# SCH-2-Main_Controls.net
KiCad netlist of a schematic drawn in Altium Designer
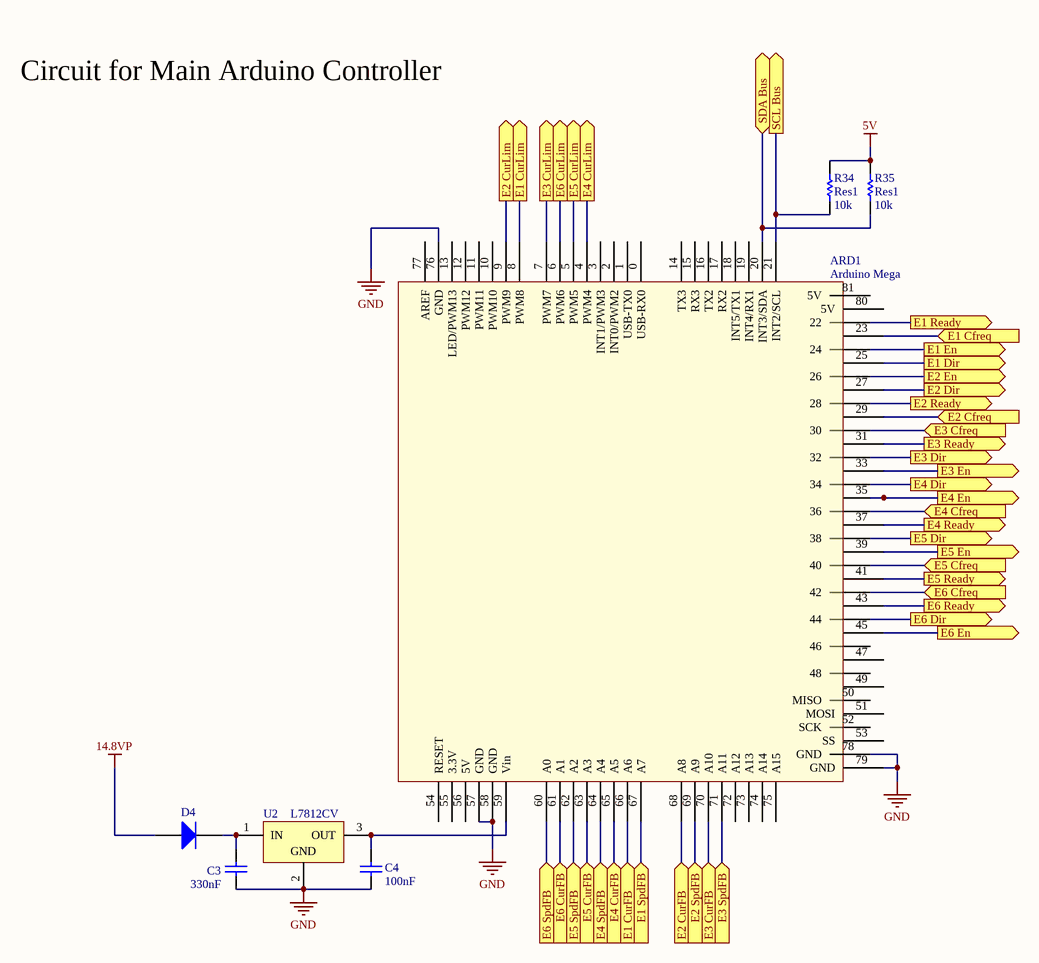
[diagram p0: SCH-2-Main Controls.SchDoc]

(export (version "E")
  (design (tool "Eeschema 10.0.6"))
  (components
    (comp (ref "ARD1")
      (value "Arduino Mega")
      (footprint "Arduino Mega")
      (libsource (lib "RSX_Schematics") (part "Arduino Mega"))
    )
    (comp (ref "C3")
      (value "330nF")
      (footprint "1608[0603]")
      (description "Capacitor")
      (fields (field (name "Comment") "Cap") (field (name "PUBLISHER") "Altium Limited"))
      (libsource (lib "Miscellaneous Devices") (part "Cap"))
    )
    (comp (ref "C4")
      (value "100nF")
      (footprint "1608[0603]")
      (description "Capacitor")
      (fields (field (name "Comment") "Cap") (field (name "PUBLISHER") "Altium Limited"))
      (libsource (lib "Miscellaneous Devices") (part "Cap"))
    )
    (comp (ref "D4")
      (value "Diode 1N4001")
      (footprint "DO-41")
      (description "1 Amp General Purpose Rectifier")
      (fields (field (name "PUBLISHER") "Altium Limited"))
      (libsource (lib "Miscellaneous Devices") (part "Diode 1N4001"))
    )
    (comp (ref "R34")
      (value "Res1")
      (footprint "RESC1608X06N_0603")
      (description "Resistor")
      (fields (field (name "ALTIUM_VALUE") "10k") (field (name "PUBLISHER") "Altium Limited"))
      (libsource (lib "RSX_Resistors") (part "Res1"))
    )
    (comp (ref "R35")
      (value "Res1")
      (footprint "RESC1608X06N_0603")
      (description "Resistor")
      (fields (field (name "ALTIUM_VALUE") "10k") (field (name "PUBLISHER") "Altium Limited"))
      (libsource (lib "RSX_Resistors") (part "Res1"))
    )
    (comp (ref "U2")
      (value "L7812CV")
      (footprint "TO220")
      (description "Positive Voltage Regulator, 12V, 3-Pin TO-220")
      (libsource (lib "Altium Content Vault") (part "PM-REG-L4940-SIL3"))
    )
  )
  (nets
    (net (code "1") (name "/E1 Cfreq") (class "Default")
      (node (ref "ARD1") (pin "23") (pinfunction "23_23") (pintype "passive"))
    )
    (net (code "2") (name "/E1 CurFB") (class "Default")
      (node (ref "ARD1") (pin "66") (pinfunction "A6_66") (pintype "passive"))
    )
    (net (code "3") (name "/E1 CurLim") (class "Default")
      (node (ref "ARD1") (pin "8") (pinfunction "PWM8_8") (pintype "passive"))
    )
    (net (code "4") (name "/E1 Dir") (class "Default")
      (node (ref "ARD1") (pin "25") (pinfunction "25_25") (pintype "passive"))
    )
    (net (code "5") (name "/E1 En") (class "Default")
      (node (ref "ARD1") (pin "24") (pinfunction "24_24") (pintype "passive"))
    )
    (net (code "6") (name "/E1 Ready") (class "Default")
      (node (ref "ARD1") (pin "22") (pinfunction "22_22") (pintype "passive"))
    )
    (net (code "7") (name "/E1 SpdFB") (class "Default")
      (node (ref "ARD1") (pin "67") (pinfunction "A7_67") (pintype "passive"))
    )
    (net (code "8") (name "/E2 Cfreq") (class "Default")
      (node (ref "ARD1") (pin "29") (pinfunction "29_29") (pintype "passive"))
    )
    (net (code "9") (name "/E2 CurFB") (class "Default")
      (node (ref "ARD1") (pin "68") (pinfunction "A8_68") (pintype "passive"))
    )
    (net (code "10") (name "/E2 CurLim") (class "Default")
      (node (ref "ARD1") (pin "9") (pinfunction "PWM9_9") (pintype "passive"))
    )
    (net (code "11") (name "/E2 Dir") (class "Default")
      (node (ref "ARD1") (pin "27") (pinfunction "27_27") (pintype "passive"))
    )
    (net (code "12") (name "/E2 En") (class "Default")
      (node (ref "ARD1") (pin "26") (pinfunction "26_26") (pintype "passive"))
    )
    (net (code "13") (name "/E2 Ready") (class "Default")
      (node (ref "ARD1") (pin "28") (pinfunction "28_28") (pintype "passive"))
    )
    (net (code "14") (name "/E2 SpdFB") (class "Default")
      (node (ref "ARD1") (pin "69") (pinfunction "A9_69") (pintype "passive"))
    )
    (net (code "15") (name "/E3 Cfreq") (class "Default")
      (node (ref "ARD1") (pin "30") (pinfunction "30_30") (pintype "passive"))
    )
    (net (code "16") (name "/E3 CurFB") (class "Default")
      (node (ref "ARD1") (pin "70") (pinfunction "A10_70") (pintype "passive"))
    )
    (net (code "17") (name "/E3 CurLim") (class "Default")
      (node (ref "ARD1") (pin "7") (pinfunction "PWM7_7") (pintype "passive"))
    )
    (net (code "18") (name "/E3 Dir") (class "Default")
      (node (ref "ARD1") (pin "32") (pinfunction "32_32") (pintype "passive"))
    )
    (net (code "19") (name "/E3 En") (class "Default")
      (node (ref "ARD1") (pin "33") (pinfunction "33_33") (pintype "passive"))
    )
    (net (code "20") (name "/E3 Ready") (class "Default")
      (node (ref "ARD1") (pin "31") (pinfunction "31_31") (pintype "passive"))
    )
    (net (code "21") (name "/E3 SpdFB") (class "Default")
      (node (ref "ARD1") (pin "71") (pinfunction "A11_71") (pintype "passive"))
    )
    (net (code "22") (name "/E4 Cfreq") (class "Default")
      (node (ref "ARD1") (pin "36") (pinfunction "36_36") (pintype "passive"))
    )
    (net (code "23") (name "/E4 CurFB") (class "Default")
      (node (ref "ARD1") (pin "65") (pinfunction "A5_65") (pintype "passive"))
    )
    (net (code "24") (name "/E4 CurLim") (class "Default")
      (node (ref "ARD1") (pin "4") (pinfunction "PWM4_4") (pintype "passive"))
    )
    (net (code "25") (name "/E4 Dir") (class "Default")
      (node (ref "ARD1") (pin "34") (pinfunction "34_34") (pintype "passive"))
    )
    (net (code "26") (name "/E4 En") (class "Default")
      (node (ref "ARD1") (pin "35") (pinfunction "35_35") (pintype "passive"))
    )
    (net (code "27") (name "/E4 Ready") (class "Default")
      (node (ref "ARD1") (pin "37") (pinfunction "37_37") (pintype "passive"))
    )
    (net (code "28") (name "/E4 SpdFB") (class "Default")
      (node (ref "ARD1") (pin "64") (pinfunction "A4_64") (pintype "passive"))
    )
    (net (code "29") (name "/E5 Cfreq") (class "Default")
      (node (ref "ARD1") (pin "40") (pinfunction "40_40") (pintype "passive"))
    )
    (net (code "30") (name "/E5 CurFB") (class "Default")
      (node (ref "ARD1") (pin "63") (pinfunction "A3_63") (pintype "passive"))
    )
    (net (code "31") (name "/E5 CurLim") (class "Default")
      (node (ref "ARD1") (pin "5") (pinfunction "PWM5_5") (pintype "passive"))
    )
    (net (code "32") (name "/E5 Dir") (class "Default")
      (node (ref "ARD1") (pin "38") (pinfunction "38_38") (pintype "passive"))
    )
    (net (code "33") (name "/E5 En") (class "Default")
      (node (ref "ARD1") (pin "39") (pinfunction "39_39") (pintype "passive"))
    )
    (net (code "34") (name "/E5 Ready") (class "Default")
      (node (ref "ARD1") (pin "41") (pinfunction "41_41") (pintype "passive"))
    )
    (net (code "35") (name "/E5 SpdFB") (class "Default")
      (node (ref "ARD1") (pin "62") (pinfunction "A2_62") (pintype "passive"))
    )
    (net (code "36") (name "/E6 Cfreq") (class "Default")
      (node (ref "ARD1") (pin "42") (pinfunction "42_42") (pintype "passive"))
    )
    (net (code "37") (name "/E6 CurFB") (class "Default")
      (node (ref "ARD1") (pin "61") (pinfunction "A1_61") (pintype "passive"))
    )
    (net (code "38") (name "/E6 CurLim") (class "Default")
      (node (ref "ARD1") (pin "6") (pinfunction "PWM6_6") (pintype "passive"))
    )
    (net (code "39") (name "/E6 Dir") (class "Default")
      (node (ref "ARD1") (pin "44") (pinfunction "44_44") (pintype "passive"))
    )
    (net (code "40") (name "/E6 En") (class "Default")
      (node (ref "ARD1") (pin "45") (pinfunction "45_45") (pintype "passive"))
    )
    (net (code "41") (name "/E6 Ready") (class "Default")
      (node (ref "ARD1") (pin "43") (pinfunction "43_43") (pintype "passive"))
    )
    (net (code "42") (name "/E6 SpdFB") (class "Default")
      (node (ref "ARD1") (pin "60") (pinfunction "A0_60") (pintype "passive"))
    )
    (net (code "43") (name "/SCL Bus") (class "Default")
      (node (ref "ARD1") (pin "21") (pinfunction "INT2/SCL_21") (pintype "passive"))
      (node (ref "R34") (pin "1") (pinfunction "1_1") (pintype "passive"))
    )
    (net (code "44") (name "/SDA Bus") (class "Default")
      (node (ref "ARD1") (pin "20") (pinfunction "INT3/SDA_20") (pintype "passive"))
      (node (ref "R35") (pin "1") (pinfunction "1_1") (pintype "passive"))
    )
    (net (code "45") (name "5V") (class "Default")
      (node (ref "R34") (pin "2") (pinfunction "2_2") (pintype "passive"))
      (node (ref "R35") (pin "2") (pinfunction "2_2") (pintype "passive"))
    )
    (net (code "46") (name "14.8VP") (class "Default")
      (node (ref "D4") (pin "1") (pinfunction "A_1") (pintype "passive"))
    )
    (net (code "47") (name "GND") (class "Default")
      (node (ref "ARD1") (pin "57") (pinfunction "GND_57") (pintype "passive"))
      (node (ref "ARD1") (pin "58") (pinfunction "GND_58") (pintype "passive"))
      (node (ref "ARD1") (pin "76") (pinfunction "GND_76") (pintype "passive"))
      (node (ref "ARD1") (pin "78") (pinfunction "GND_78") (pintype "passive"))
      (node (ref "ARD1") (pin "79") (pinfunction "GND_79") (pintype "passive"))
      (node (ref "C3") (pin "2") (pinfunction "2_2") (pintype "passive"))
      (node (ref "C4") (pin "2") (pinfunction "2_2") (pintype "passive"))
      (node (ref "U2") (pin "2") (pinfunction "GND_2") (pintype "power_in"))
    )
    (net (code "48") (name "Net-(ARD1-Vin)") (class "Default")
      (node (ref "ARD1") (pin "59") (pinfunction "Vin_59") (pintype "passive"))
      (node (ref "C4") (pin "1") (pinfunction "1_1") (pintype "passive"))
      (node (ref "U2") (pin "3") (pinfunction "OUT_3") (pintype "power_in"))
    )
    (net (code "49") (name "Net-(D4-K)") (class "Default")
      (node (ref "C3") (pin "1") (pinfunction "1_1") (pintype "passive"))
      (node (ref "D4") (pin "2") (pinfunction "K_2") (pintype "passive"))
      (node (ref "U2") (pin "1") (pinfunction "IN_1") (pintype "power_in"))
    )
    (net (code "50") (name "unconnected-(ARD1-3.3V-Pad55)") (class "Default")
      (node (ref "ARD1") (pin "55") (pinfunction "3.3V_55") (pintype "passive"))
    )
    (net (code "51") (name "unconnected-(ARD1-5V-Pad56)") (class "Default")
      (node (ref "ARD1") (pin "56") (pinfunction "5V_56") (pintype "passive"))
    )
    (net (code "52") (name "unconnected-(ARD1-5V-Pad80)") (class "Default")
      (node (ref "ARD1") (pin "80") (pinfunction "5V_80") (pintype "passive"))
    )
    (net (code "53") (name "unconnected-(ARD1-5V-Pad81)") (class "Default")
      (node (ref "ARD1") (pin "81") (pinfunction "5V_81") (pintype "passive"))
    )
    (net (code "54") (name "unconnected-(ARD1-A12-Pad72)") (class "Default")
      (node (ref "ARD1") (pin "72") (pinfunction "A12_72") (pintype "passive"))
    )
    (net (code "55") (name "unconnected-(ARD1-A13-Pad73)") (class "Default")
      (node (ref "ARD1") (pin "73") (pinfunction "A13_73") (pintype "passive"))
    )
    (net (code "56") (name "unconnected-(ARD1-A14-Pad74)") (class "Default")
      (node (ref "ARD1") (pin "74") (pinfunction "A14_74") (pintype "passive"))
    )
    (net (code "57") (name "unconnected-(ARD1-A15-Pad75)") (class "Default")
      (node (ref "ARD1") (pin "75") (pinfunction "A15_75") (pintype "passive"))
    )
    (net (code "58") (name "unconnected-(ARD1-AREF-Pad77)") (class "Default")
      (node (ref "ARD1") (pin "77") (pinfunction "AREF_77") (pintype "passive"))
    )
    (net (code "59") (name "unconnected-(ARD1-INT0{slash}PWM2-Pad2)") (class "Default")
      (node (ref "ARD1") (pin "2") (pinfunction "INT0/PWM2_2") (pintype "passive"))
    )
    (net (code "60") (name "unconnected-(ARD1-INT1{slash}PWM3-Pad3)") (class "Default")
      (node (ref "ARD1") (pin "3") (pinfunction "INT1/PWM3_3") (pintype "passive"))
    )
    (net (code "61") (name "unconnected-(ARD1-INT4{slash}RX1-Pad19)") (class "Default")
      (node (ref "ARD1") (pin "19") (pinfunction "INT4/RX1_19") (pintype "passive"))
    )
    (net (code "62") (name "unconnected-(ARD1-INT5{slash}TX1-Pad18)") (class "Default")
      (node (ref "ARD1") (pin "18") (pinfunction "INT5/TX1_18") (pintype "passive"))
    )
    (net (code "63") (name "unconnected-(ARD1-LED{slash}PWM13-Pad13)") (class "Default")
      (node (ref "ARD1") (pin "13") (pinfunction "LED/PWM13_13") (pintype "passive"))
    )
    (net (code "64") (name "unconnected-(ARD1-MISO-Pad50)") (class "Default")
      (node (ref "ARD1") (pin "50") (pinfunction "MISO_50") (pintype "passive"))
    )
    (net (code "65") (name "unconnected-(ARD1-MOSI-Pad51)") (class "Default")
      (node (ref "ARD1") (pin "51") (pinfunction "MOSI_51") (pintype "passive"))
    )
    (net (code "66") (name "unconnected-(ARD1-PWM10-Pad10)") (class "Default")
      (node (ref "ARD1") (pin "10") (pinfunction "PWM10_10") (pintype "passive"))
    )
    (net (code "67") (name "unconnected-(ARD1-PWM11-Pad11)") (class "Default")
      (node (ref "ARD1") (pin "11") (pinfunction "PWM11_11") (pintype "passive"))
    )
    (net (code "68") (name "unconnected-(ARD1-PWM12-Pad12)") (class "Default")
      (node (ref "ARD1") (pin "12") (pinfunction "PWM12_12") (pintype "passive"))
    )
    (net (code "69") (name "unconnected-(ARD1-Pad46)") (class "Default")
      (node (ref "ARD1") (pin "46") (pinfunction "46_46") (pintype "passive"))
    )
    (net (code "70") (name "unconnected-(ARD1-Pad47)") (class "Default")
      (node (ref "ARD1") (pin "47") (pinfunction "47_47") (pintype "passive"))
    )
    (net (code "71") (name "unconnected-(ARD1-Pad48)") (class "Default")
      (node (ref "ARD1") (pin "48") (pinfunction "48_48") (pintype "passive"))
    )
    (net (code "72") (name "unconnected-(ARD1-Pad49)") (class "Default")
      (node (ref "ARD1") (pin "49") (pinfunction "49_49") (pintype "passive"))
    )
    (net (code "73") (name "unconnected-(ARD1-RESET-Pad54)") (class "Default")
      (node (ref "ARD1") (pin "54") (pinfunction "RESET_54") (pintype "passive"))
    )
    (net (code "74") (name "unconnected-(ARD1-RX2-Pad17)") (class "Default")
      (node (ref "ARD1") (pin "17") (pinfunction "RX2_17") (pintype "passive"))
    )
    (net (code "75") (name "unconnected-(ARD1-RX3-Pad15)") (class "Default")
      (node (ref "ARD1") (pin "15") (pinfunction "RX3_15") (pintype "passive"))
    )
    (net (code "76") (name "unconnected-(ARD1-SCK-Pad52)") (class "Default")
      (node (ref "ARD1") (pin "52") (pinfunction "SCK_52") (pintype "passive"))
    )
    (net (code "77") (name "unconnected-(ARD1-SS-Pad53)") (class "Default")
      (node (ref "ARD1") (pin "53") (pinfunction "SS_53") (pintype "passive"))
    )
    (net (code "78") (name "unconnected-(ARD1-TX2-Pad16)") (class "Default")
      (node (ref "ARD1") (pin "16") (pinfunction "TX2_16") (pintype "passive"))
    )
    (net (code "79") (name "unconnected-(ARD1-TX3-Pad14)") (class "Default")
      (node (ref "ARD1") (pin "14") (pinfunction "TX3_14") (pintype "passive"))
    )
    (net (code "80") (name "unconnected-(ARD1-USB-RX0-Pad0)") (class "Default")
      (node (ref "ARD1") (pin "0") (pinfunction "USB-RX0_0") (pintype "passive"))
    )
    (net (code "81") (name "unconnected-(ARD1-USB-TX0-Pad1)") (class "Default")
      (node (ref "ARD1") (pin "1") (pinfunction "USB-TX0_1") (pintype "passive"))
    )
  )
)
